# demod_blank.net
KiCad netlist of a schematic drawn in Altium Designer
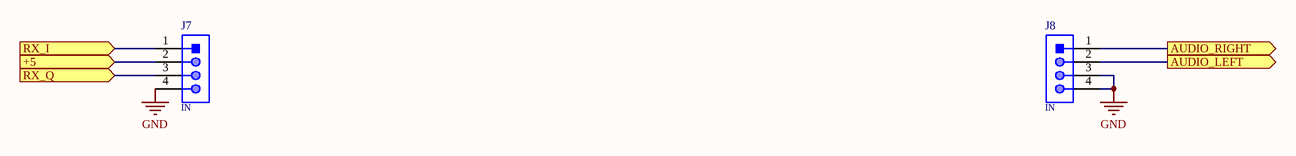
[diagram p0: demod_blank.SchDoc]

(export (version "E")
  (design (tool "Eeschema 10.0.6"))
  (components
    (comp (ref "J7")
      (value "IN")
      (footprint "61300411121")
      (description "THT Vertical Pin Header WR-PHD, Pitch 2.54 mm, Single Row, 4 pins")
      (fields
        (field (name "MANUFACTURER") "Wurth Elektronik")
        (field (name "PART NUMBER") "61300411121")
        (field (name "PUBLISHER") "WurthElektronik")
      )
      (libsource (lib "Altium Content Vault") (part "WE-CN-1P-M-R4"))
    )
    (comp (ref "J8")
      (value "IN")
      (footprint "61300411121")
      (description "THT Vertical Pin Header WR-PHD, Pitch 2.54 mm, Single Row, 4 pins")
      (fields
        (field (name "MANUFACTURER") "Wurth Elektronik")
        (field (name "PART NUMBER") "61300411121")
        (field (name "PUBLISHER") "WurthElektronik")
      )
      (libsource (lib "") (part "WE-CN-1P-M-R4_1"))
    )
  )
  (nets
    (net (code "1") (name "/+5") (class "Default")
      (node (ref "J7") (pin "2") (pinfunction "2_2") (pintype "passive"))
    )
    (net (code "2") (name "/AUDIO_LEFT") (class "Default")
      (node (ref "J8") (pin "2") (pinfunction "2_2") (pintype "passive"))
    )
    (net (code "3") (name "/AUDIO_RIGHT") (class "Default")
      (node (ref "J8") (pin "1") (pinfunction "1_1") (pintype "passive"))
    )
    (net (code "4") (name "/RX_I") (class "Default")
      (node (ref "J7") (pin "1") (pinfunction "1_1") (pintype "passive"))
    )
    (net (code "5") (name "/RX_Q") (class "Default")
      (node (ref "J7") (pin "3") (pinfunction "3_3") (pintype "passive"))
    )
    (net (code "6") (name "GND") (class "Default")
      (node (ref "J7") (pin "4") (pinfunction "4_4") (pintype "passive"))
      (node (ref "J8") (pin "3") (pinfunction "3_3") (pintype "passive"))
      (node (ref "J8") (pin "4") (pinfunction "4_4") (pintype "passive"))
    )
  )
)
